# LEDMatrix_Schematic.net
KiCad netlist of a schematic drawn in Altium Designer
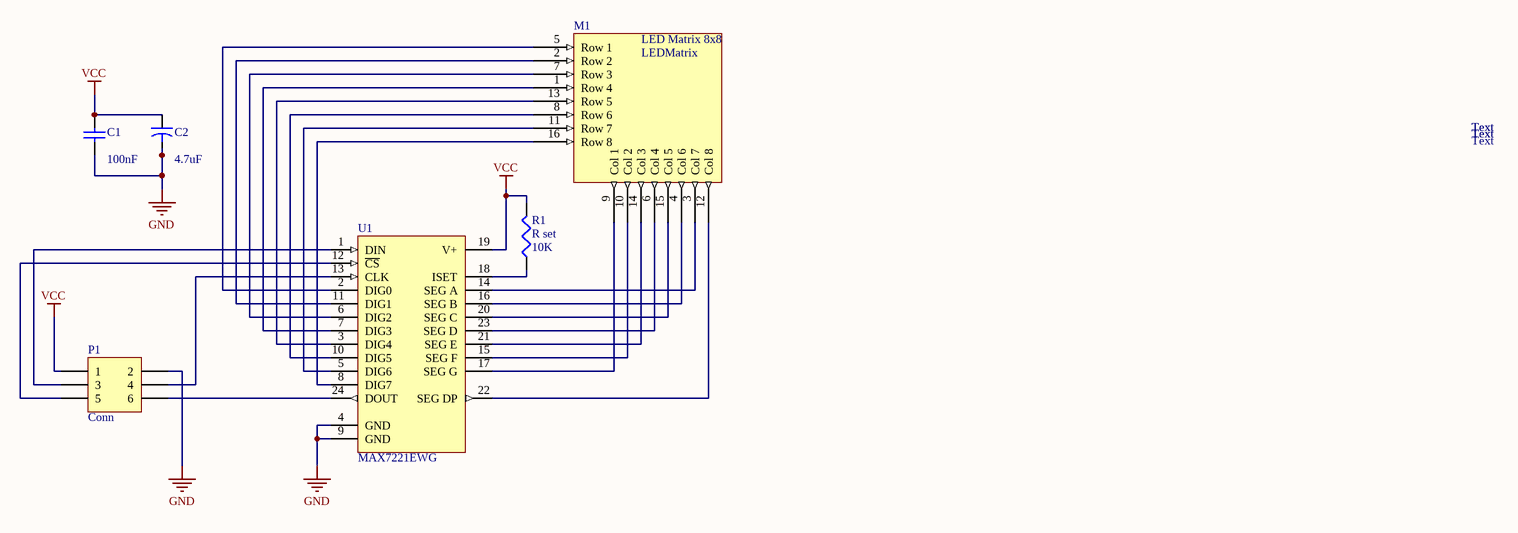
[diagram p0: LEDMatrix_Schematic.SchDoc]

(export (version "E")
  (design (tool "Eeschema 10.0.6"))
  (components
    (comp (ref "C1")
      (value "100nF")
      (footprint "C1206")
      (description "Capacitor (Semiconductor SIM Model)")
      (fields (field (name "PUBLISHER") "Altium Limited"))
      (libsource (lib "Miscellaneous Devices") (part "Cap Semi"))
    )
    (comp (ref "C2")
      (value "4.7uF")
      (footprint "CAPR5-4X5")
      (description "Capacitor")
      (fields (field (name "PUBLISHER") "Altium Limited"))
      (libsource (lib "Miscellaneous Devices") (part "Cap2"))
    )
    (comp (ref "M1")
      (value "LEDMatrix")
      (footprint "LEDMATRIX")
      (description "LED Matrix 8x8 white")
      (libsource (lib "LEDMatrix") (part "LEDMatrix"))
    )
    (comp (ref "P1")
      (value "Conn")
      (footprint "HDR2X3H")
      (description "Header, 3-Pin, Dual row, Right Angle")
      (fields (field (name "PUBLISHER") "Altium Limited"))
      (libsource (lib "Miscellaneous Connectors") (part "Header 3X2H"))
    )
    (comp (ref "R1")
      (value "R set")
      (footprint "RESC2012N")
      (description "Resistor")
      (fields (field (name "ALTIUM_VALUE") "10K") (field (name "PUBLISHER") "Altium Limited"))
      (libsource (lib "Miscellaneous Devices") (part "Res3"))
    )
    (comp (ref "U1")
      (value "MAX7221EWG")
      (footprint "WSO24_N")
      (description "Serially Interfaced, 8-Digit LED Display Driver")
      (fields (field (name "PUBLISHER") "Altium Limited"))
      (libsource (lib "Maxim Interface Display Driver") (part "MAX7221EWG"))
    )
  )
  (nets
    (net (code "1") (name "GND") (class "Default")
      (node (ref "C1") (pin "1") (pinfunction "1_1") (pintype "passive"))
      (node (ref "C2") (pin "2") (pinfunction "2_2") (pintype "passive"))
      (node (ref "P1") (pin "2") (pinfunction "2_2") (pintype "passive"))
      (node (ref "U1") (pin "4") (pinfunction "GND_4") (pintype "power_in"))
      (node (ref "U1") (pin "9") (pinfunction "GND_9") (pintype "power_in"))
    )
    (net (code "2") (name "Net-(M1-Col_1)") (class "Default")
      (node (ref "M1") (pin "9") (pinfunction "Col_1_9") (pintype "output"))
      (node (ref "U1") (pin "17") (pinfunction "SEG_G_17") (pintype "tri_state"))
    )
    (net (code "3") (name "Net-(M1-Col_2)") (class "Default")
      (node (ref "M1") (pin "10") (pinfunction "Col_2_10") (pintype "output"))
      (node (ref "U1") (pin "15") (pinfunction "SEG_F_15") (pintype "tri_state"))
    )
    (net (code "4") (name "Net-(M1-Col_3)") (class "Default")
      (node (ref "M1") (pin "14") (pinfunction "Col_3_14") (pintype "output"))
      (node (ref "U1") (pin "21") (pinfunction "SEG_E_21") (pintype "tri_state"))
    )
    (net (code "5") (name "Net-(M1-Col_4)") (class "Default")
      (node (ref "M1") (pin "6") (pinfunction "Col_4_6") (pintype "output"))
      (node (ref "U1") (pin "23") (pinfunction "SEG_D_23") (pintype "tri_state"))
    )
    (net (code "6") (name "Net-(M1-Col_5)") (class "Default")
      (node (ref "M1") (pin "15") (pinfunction "Col_5_15") (pintype "output"))
      (node (ref "U1") (pin "20") (pinfunction "SEG_C_20") (pintype "tri_state"))
    )
    (net (code "7") (name "Net-(M1-Col_6)") (class "Default")
      (node (ref "M1") (pin "4") (pinfunction "Col_6_4") (pintype "output"))
      (node (ref "U1") (pin "16") (pinfunction "SEG_B_16") (pintype "tri_state"))
    )
    (net (code "8") (name "Net-(M1-Col_7)") (class "Default")
      (node (ref "M1") (pin "3") (pinfunction "Col_7_3") (pintype "output"))
      (node (ref "U1") (pin "14") (pinfunction "SEG_A_14") (pintype "tri_state"))
    )
    (net (code "9") (name "Net-(M1-Col_8)") (class "Default")
      (node (ref "M1") (pin "12") (pinfunction "Col_8_12") (pintype "output"))
      (node (ref "U1") (pin "22") (pinfunction "SEG_DP_22") (pintype "output"))
    )
    (net (code "10") (name "Net-(M1-Row_1)") (class "Default")
      (node (ref "M1") (pin "5") (pinfunction "Row_1_5") (pintype "input"))
      (node (ref "U1") (pin "2") (pinfunction "DIG0_2") (pintype "tri_state"))
    )
    (net (code "11") (name "Net-(M1-Row_2)") (class "Default")
      (node (ref "M1") (pin "2") (pinfunction "Row_2_2") (pintype "input"))
      (node (ref "U1") (pin "11") (pinfunction "DIG1_11") (pintype "tri_state"))
    )
    (net (code "12") (name "Net-(M1-Row_3)") (class "Default")
      (node (ref "M1") (pin "7") (pinfunction "Row_3_7") (pintype "input"))
      (node (ref "U1") (pin "6") (pinfunction "DIG2_6") (pintype "tri_state"))
    )
    (net (code "13") (name "Net-(M1-Row_4)") (class "Default")
      (node (ref "M1") (pin "1") (pinfunction "Row_4_1") (pintype "input"))
      (node (ref "U1") (pin "7") (pinfunction "DIG3_7") (pintype "tri_state"))
    )
    (net (code "14") (name "Net-(M1-Row_5)") (class "Default")
      (node (ref "M1") (pin "13") (pinfunction "Row_5_13") (pintype "input"))
      (node (ref "U1") (pin "3") (pinfunction "DIG4_3") (pintype "tri_state"))
    )
    (net (code "15") (name "Net-(M1-Row_6)") (class "Default")
      (node (ref "M1") (pin "8") (pinfunction "Row_6_8") (pintype "input"))
      (node (ref "U1") (pin "10") (pinfunction "DIG5_10") (pintype "tri_state"))
    )
    (net (code "16") (name "Net-(M1-Row_7)") (class "Default")
      (node (ref "M1") (pin "11") (pinfunction "Row_7_11") (pintype "input"))
      (node (ref "U1") (pin "5") (pinfunction "DIG6_5") (pintype "tri_state"))
    )
    (net (code "17") (name "Net-(M1-Row_8)") (class "Default")
      (node (ref "M1") (pin "16") (pinfunction "Row_8_16") (pintype "input"))
      (node (ref "U1") (pin "8") (pinfunction "DIG7_8") (pintype "tri_state"))
    )
    (net (code "18") (name "Net-(U1-CLK)") (class "Default")
      (node (ref "P1") (pin "4") (pinfunction "4_4") (pintype "passive"))
      (node (ref "U1") (pin "13") (pinfunction "CLK_13") (pintype "input"))
    )
    (net (code "19") (name "Net-(U1-DIN)") (class "Default")
      (node (ref "P1") (pin "3") (pinfunction "3_3") (pintype "passive"))
      (node (ref "U1") (pin "1") (pinfunction "DIN_1") (pintype "input"))
    )
    (net (code "20") (name "Net-(U1-DOUT)") (class "Default")
      (node (ref "P1") (pin "6") (pinfunction "6_6") (pintype "passive"))
      (node (ref "U1") (pin "24") (pinfunction "DOUT_24") (pintype "output"))
    )
    (net (code "21") (name "Net-(U1-ISET)") (class "Default")
      (node (ref "R1") (pin "1") (pinfunction "1_1") (pintype "passive"))
      (node (ref "U1") (pin "18") (pinfunction "ISET_18") (pintype "passive"))
    )
    (net (code "22") (name "Net-(U1-~{CS})") (class "Default")
      (node (ref "P1") (pin "5") (pinfunction "5_5") (pintype "passive"))
      (node (ref "U1") (pin "12") (pinfunction "~{CS}_12") (pintype "input"))
    )
    (net (code "23") (name "VCC") (class "Default")
      (node (ref "C1") (pin "2") (pinfunction "2_2") (pintype "passive"))
      (node (ref "C2") (pin "1") (pinfunction "1_1") (pintype "passive"))
      (node (ref "P1") (pin "1") (pinfunction "1_1") (pintype "passive"))
      (node (ref "R1") (pin "2") (pinfunction "2_2") (pintype "passive"))
      (node (ref "U1") (pin "19") (pinfunction "V+_19") (pintype "power_in"))
    )
  )
)
